# HIZ12.net
KiCad netlist of a schematic drawn in EAGLE
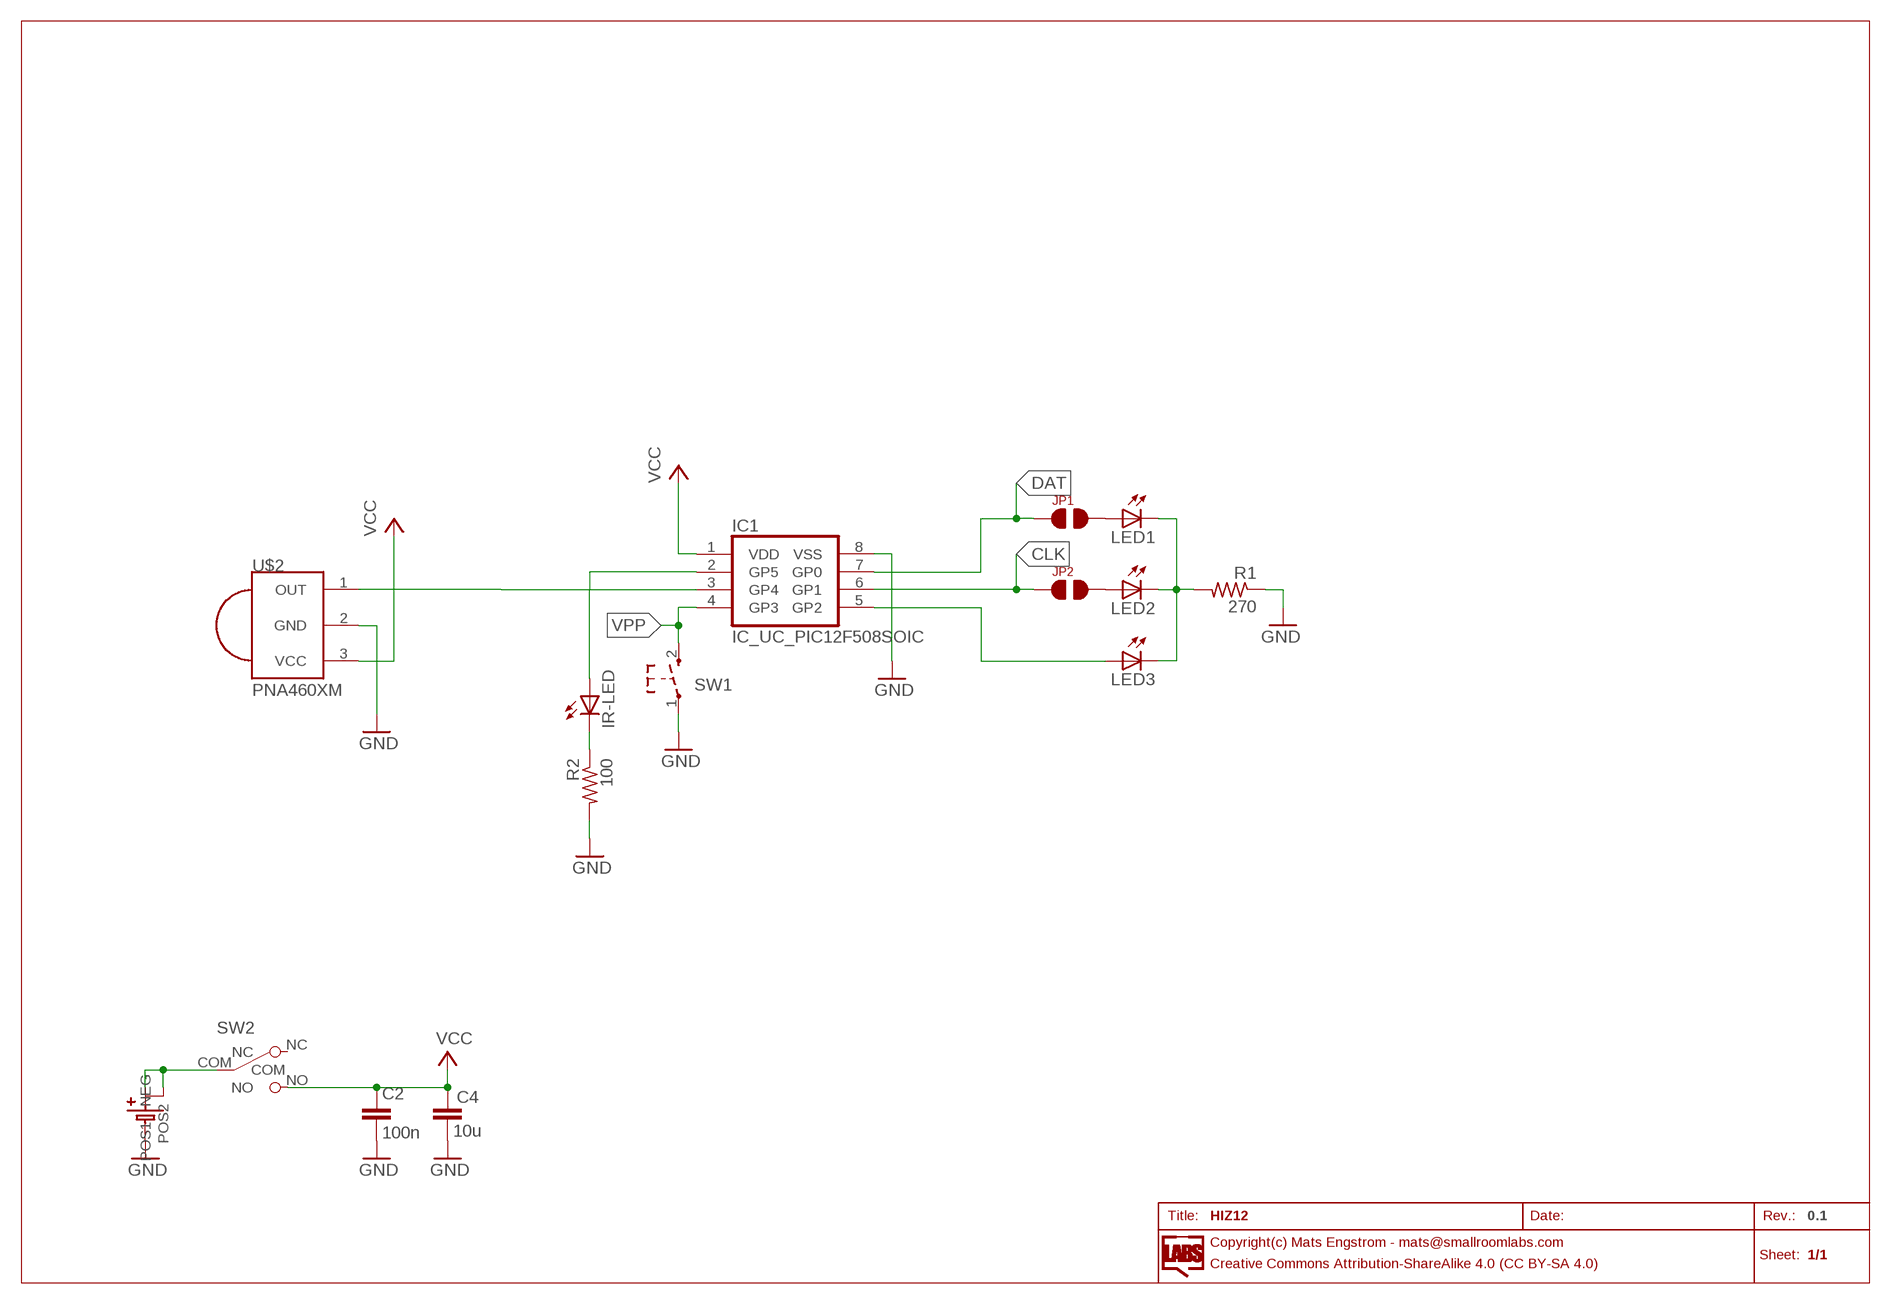
[diagram p0: schematic, sheet 1]

(export (version "E")
  (design (tool "Eeschema 10.0.6"))
  (components
    (comp (ref "C2")
      (value "100n")
      (footprint "eagle-import:C805")
      (libsource (lib "eagle-import") (part "CAPACITOR_NPOL-0805"))
    )
    (comp (ref "C4")
      (value "10u")
      (footprint "eagle-import:C805")
      (libsource (lib "eagle-import") (part "CAPACITOR_NPOL-0805"))
    )
    (comp (ref "IC1")
      (value "IC_UC_PIC12F508SOIC")
      (footprint "eagle-import:SO-8")
      (libsource (lib "eagle-import") (part "IC_UC_PIC12F508SOIC"))
    )
    (comp (ref "IR-LED")
      (value "LEDSMT1206")
      (footprint "eagle-import:1206")
      (libsource (lib "eagle-import") (part "LEDSMT1206"))
    )
    (comp (ref "JP1")
      (value "JP2-TINY")
      (footprint "eagle-import:JP2-T")
      (libsource (lib "eagle-import") (part "JP2-TINY"))
    )
    (comp (ref "JP2")
      (value "JP2-TINY")
      (footprint "eagle-import:JP2-T")
      (libsource (lib "eagle-import") (part "JP2-TINY"))
    )
    (comp (ref "LED1")
      (value "LED-0805")
      (footprint "eagle-import:LED-805")
      (libsource (lib "eagle-import") (part "LED-0805"))
    )
    (comp (ref "LED2")
      (value "LED-0805")
      (footprint "eagle-import:LED-805")
      (libsource (lib "eagle-import") (part "LED-0805"))
    )
    (comp (ref "LED3")
      (value "LED-0805")
      (footprint "eagle-import:LED-805")
      (libsource (lib "eagle-import") (part "LED-0805"))
    )
    (comp (ref "R1")
      (value "270")
      (footprint "eagle-import:R0805")
      (libsource (lib "eagle-import") (part "R-0805"))
    )
    (comp (ref "R2")
      (value "100")
      (footprint "eagle-import:R0805")
      (libsource (lib "eagle-import") (part "R-0805"))
    )
    (comp (ref "SW1")
      (value "SW_TACT_2P-3X6")
      (footprint "eagle-import:SW_TACT_3X6")
      (libsource (lib "eagle-import") (part "SW_TACT_2P-3X6"))
    )
    (comp (ref "SW2")
      (value "SW_SLIDE")
      (footprint "eagle-import:SLIDE_SWITCH_SMD")
      (libsource (lib "eagle-import") (part "SW_SLIDE"))
    )
    (comp (ref "U$2")
      (value "PNA460XM")
      (footprint "eagle-import:PNA460XM")
      (libsource (lib "eagle-import") (part "PNA460XM"))
    )
    (comp (ref "U$3")
      (value "BATTERYCOIN-12MM-SMD")
      (footprint "eagle-import:CR1220-SMD")
      (libsource (lib "eagle-import") (part "BATTERYCOIN-12MM-SMD"))
    )
  )
  (nets
    (net (code "1") (name "CLK") (class "Default")
      (node (ref "IC1") (pin "6") (pinfunction "GP1_6") (pintype "bidirectional"))
      (node (ref "JP2") (pin "P$1") (pinfunction "P$1_P$1") (pintype "bidirectional"))
    )
    (net (code "2") (name "DAT") (class "Default")
      (node (ref "IC1") (pin "7") (pinfunction "GP0_7") (pintype "bidirectional"))
      (node (ref "JP1") (pin "P$1") (pinfunction "P$1_P$1") (pintype "bidirectional"))
    )
    (net (code "3") (name "GND") (class "Default")
      (node (ref "C2") (pin "2") (pinfunction "2_2") (pintype "passive"))
      (node (ref "C4") (pin "2") (pinfunction "2_2") (pintype "passive"))
      (node (ref "IC1") (pin "8") (pinfunction "VSS_8") (pintype "power_in"))
      (node (ref "R1") (pin "1") (pinfunction "1_1") (pintype "passive"))
      (node (ref "R2") (pin "2") (pinfunction "2_2") (pintype "passive"))
      (node (ref "SW1") (pin "1") (pinfunction "1_1") (pintype "passive"))
      (node (ref "U$2") (pin "2") (pinfunction "GND_2") (pintype "power_in"))
      (node (ref "U$3") (pin "-") (pinfunction "NEG_-") (pintype "power_in"))
    )
    (net (code "4") (name "Net-(IC1-GP2)") (class "Default")
      (node (ref "IC1") (pin "5") (pinfunction "GP2_5") (pintype "bidirectional"))
      (node (ref "LED3") (pin "A") (pinfunction "A_A") (pintype "passive"))
    )
    (net (code "5") (name "Net-(IC1-GP4)") (class "Default")
      (node (ref "IC1") (pin "3") (pinfunction "GP4_3") (pintype "bidirectional"))
      (node (ref "U$2") (pin "1") (pinfunction "OUT_1") (pintype "output"))
    )
    (net (code "6") (name "Net-(IC1-GP5)") (class "Default")
      (node (ref "IC1") (pin "2") (pinfunction "GP5_2") (pintype "bidirectional"))
      (node (ref "IR-LED") (pin "A") (pinfunction "A_A") (pintype "passive"))
    )
    (net (code "7") (name "Net-(IR-LED-PadC)") (class "Default")
      (node (ref "IR-LED") (pin "C") (pinfunction "C_C") (pintype "passive"))
      (node (ref "R2") (pin "1") (pinfunction "1_1") (pintype "passive"))
    )
    (net (code "8") (name "Net-(JP1-PadP$2)") (class "Default")
      (node (ref "JP1") (pin "P$2") (pinfunction "P$2_P$2") (pintype "bidirectional"))
      (node (ref "LED1") (pin "A") (pinfunction "A_A") (pintype "passive"))
    )
    (net (code "9") (name "Net-(JP2-PadP$2)") (class "Default")
      (node (ref "JP2") (pin "P$2") (pinfunction "P$2_P$2") (pintype "bidirectional"))
      (node (ref "LED2") (pin "A") (pinfunction "A_A") (pintype "passive"))
    )
    (net (code "10") (name "Net-(LED1-PadC)") (class "Default")
      (node (ref "LED1") (pin "C") (pinfunction "C_C") (pintype "passive"))
      (node (ref "LED2") (pin "C") (pinfunction "C_C") (pintype "passive"))
      (node (ref "LED3") (pin "C") (pinfunction "C_C") (pintype "passive"))
      (node (ref "R1") (pin "2") (pinfunction "2_2") (pintype "passive"))
    )
    (net (code "11") (name "Net-(U$3-POS1)") (class "Default")
      (node (ref "SW2") (pin "COM") (pinfunction "COM_COM") (pintype "passive"))
      (node (ref "U$3") (pin "+$1") (pinfunction "POS1_+$1") (pintype "power_in"))
      (node (ref "U$3") (pin "+$2") (pinfunction "POS2_+$2") (pintype "power_in"))
    )
    (net (code "12") (name "VCC") (class "Default")
      (node (ref "C2") (pin "1") (pinfunction "1_1") (pintype "passive"))
      (node (ref "C4") (pin "1") (pinfunction "1_1") (pintype "passive"))
      (node (ref "IC1") (pin "1") (pinfunction "VDD_1") (pintype "power_in"))
      (node (ref "SW2") (pin "NO") (pinfunction "NO_NO") (pintype "passive"))
      (node (ref "U$2") (pin "3") (pinfunction "VCC_3") (pintype "power_in"))
    )
    (net (code "13") (name "VPP") (class "Default")
      (node (ref "IC1") (pin "4") (pinfunction "GP3_4") (pintype "bidirectional"))
      (node (ref "SW1") (pin "2") (pinfunction "3_2") (pintype "passive"))
    )
    (net (code "14") (name "unconnected-(SW2-PadNC)") (class "Default")
      (node (ref "SW2") (pin "NC") (pinfunction "NC_NC") (pintype "passive"))
    )
  )
)
